# micro.net
KiCad netlist of a schematic drawn in Altium Designer
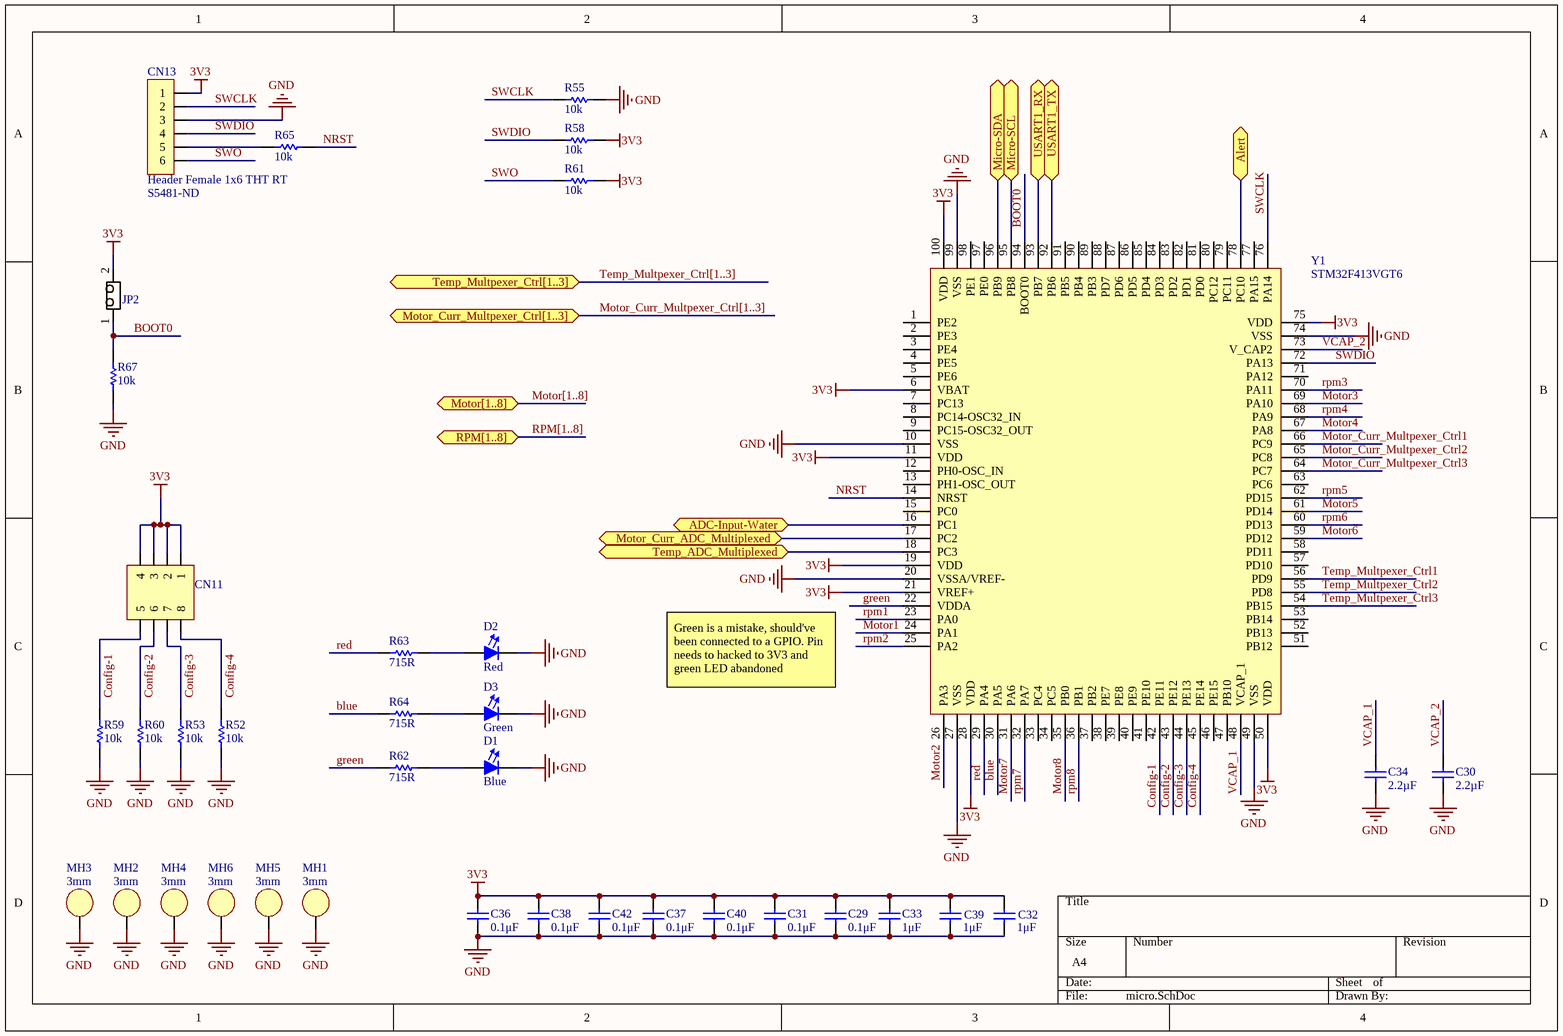
[diagram p0: micro.SchDoc]

(export (version "E")
  (design (tool "Eeschema 10.0.6"))
  (components
    (comp (ref "C29")
      (value "0.1μF")
      (footprint "CAPC1608N(0603\")")
      (description "Capacitor, Ceramic, 100V, +/- 10%, 0603 SMD, X7R")
      (fields
        (field (name "MFG") "TDK")
        (field (name "PUBLISHER") "AUVic")
        (field (name "CREATED BY") "Ashwin Sira")
      )
      (libsource (lib "AUVic_Integrated_Library_Capacitors") (part "0.1uF 100V 0603 SMD, Ceramic"))
    )
    (comp (ref "C30")
      (value "2.2µF")
      (footprint "CAPC1608N(0603\")")
      (description "Capacitor, Ceramic, 50V, 10%, 0603 SMD, X5R")
      (fields (field (name "MADE BY") "*") (field (name "PUBLISHER") "AUVic"))
      (libsource (lib "AUVic_Integrated_Library_Capacitors") (part "2.2uF, 50V, 0603 SMD, X5R, Ceramic"))
    )
    (comp (ref "C31")
      (value "0.1μF")
      (footprint "CAPC1608N(0603\")")
      (description "Capacitor, Ceramic, 100V, +/- 10%, 0603 SMD, X7R")
      (fields
        (field (name "MFG") "TDK")
        (field (name "PUBLISHER") "AUVic")
        (field (name "CREATED BY") "Ashwin Sira")
      )
      (libsource (lib "AUVic_Integrated_Library_Capacitors") (part "0.1uF 100V 0603 SMD, Ceramic"))
    )
    (comp (ref "C32")
      (value "1μF")
      (footprint "CAPC1608N(0603\")")
      (description "Capacitor, Ceramic, 25V, +/- 10%, 0603 SMD, X5R")
      (fields
        (field (name "MFG") "Murata-Electronics-North-America")
        (field (name "PUBLISHER") "AUVic")
        (field (name "CREATED BY") "Andy Bates")
      )
      (libsource (lib "AUVic_Integrated_Library_Capacitors") (part "1uF 25V 0603 SMD, Ceramic"))
    )
    (comp (ref "C33")
      (value "1μF")
      (footprint "CAPC1608N(0603\")")
      (description "Capacitor, Ceramic, 25V, +/- 10%, 0603 SMD, X5R")
      (fields
        (field (name "MFG") "Murata-Electronics-North-America")
        (field (name "PUBLISHER") "AUVic")
        (field (name "CREATED BY") "Andy Bates")
      )
      (libsource (lib "AUVic_Integrated_Library_Capacitors") (part "1uF 25V 0603 SMD, Ceramic"))
    )
    (comp (ref "C34")
      (value "2.2µF")
      (footprint "CAPC1608N(0603\")")
      (description "Capacitor, Ceramic, 50V, 10%, 0603 SMD, X5R")
      (fields (field (name "MADE BY") "*") (field (name "PUBLISHER") "AUVic"))
      (libsource (lib "AUVic_Integrated_Library_Capacitors") (part "2.2uF, 50V, 0603 SMD, X5R, Ceramic"))
    )
    (comp (ref "C36")
      (value "0.1μF")
      (footprint "CAPC1608N(0603\")")
      (description "Capacitor, Ceramic, 100V, +/- 10%, 0603 SMD, X7R")
      (fields
        (field (name "MFG") "TDK")
        (field (name "PUBLISHER") "AUVic")
        (field (name "CREATED BY") "Ashwin Sira")
      )
      (libsource (lib "AUVic_Integrated_Library_Capacitors") (part "0.1uF 100V 0603 SMD, Ceramic"))
    )
    (comp (ref "C37")
      (value "0.1μF")
      (footprint "CAPC1608N(0603\")")
      (description "Capacitor, Ceramic, 100V, +/- 10%, 0603 SMD, X7R")
      (fields
        (field (name "MFG") "TDK")
        (field (name "PUBLISHER") "AUVic")
        (field (name "CREATED BY") "Ashwin Sira")
      )
      (libsource (lib "AUVic_Integrated_Library_Capacitors") (part "0.1uF 100V 0603 SMD, Ceramic"))
    )
    (comp (ref "C38")
      (value "0.1μF")
      (footprint "CAPC1608N(0603\")")
      (description "Capacitor, Ceramic, 100V, +/- 10%, 0603 SMD, X7R")
      (fields
        (field (name "MFG") "TDK")
        (field (name "PUBLISHER") "AUVic")
        (field (name "CREATED BY") "Ashwin Sira")
      )
      (libsource (lib "AUVic_Integrated_Library_Capacitors") (part "0.1uF 100V 0603 SMD, Ceramic"))
    )
    (comp (ref "C39")
      (value "1μF")
      (footprint "CAPC1608N(0603\")")
      (description "Capacitor, Ceramic, 25V, +/- 10%, 0603 SMD, X5R")
      (fields
        (field (name "MFG") "Murata-Electronics-North-America")
        (field (name "PUBLISHER") "AUVic")
        (field (name "CREATED BY") "Andy Bates")
      )
      (libsource (lib "AUVic_Integrated_Library_Capacitors") (part "1uF 25V 0603 SMD, Ceramic"))
    )
    (comp (ref "C40")
      (value "0.1μF")
      (footprint "CAPC1608N(0603\")")
      (description "Capacitor, Ceramic, 100V, +/- 10%, 0603 SMD, X7R")
      (fields
        (field (name "MFG") "TDK")
        (field (name "PUBLISHER") "AUVic")
        (field (name "CREATED BY") "Ashwin Sira")
      )
      (libsource (lib "AUVic_Integrated_Library_Capacitors") (part "0.1uF 100V 0603 SMD, Ceramic"))
    )
    (comp (ref "C42")
      (value "0.1μF")
      (footprint "CAPC1608N(0603\")")
      (description "Capacitor, Ceramic, 100V, +/- 10%, 0603 SMD, X7R")
      (fields
        (field (name "MFG") "TDK")
        (field (name "PUBLISHER") "AUVic")
        (field (name "CREATED BY") "Ashwin Sira")
      )
      (libsource (lib "AUVic_Integrated_Library_Capacitors") (part "0.1uF 100V 0603 SMD, Ceramic"))
    )
    (comp (ref "CN11")
      (value "Header, Male, 2x4, Pitch: 0.1\" (2.54mm), THT")
      (footprint "Header, Male, 2x4, Pitch: 0.1\" (2.54mm),THT")
      (fields
        (field (name "PUBLISHER") "AUVic")
        (field (name "REVIEWED BY") "*")
        (field (name "CREATED BY") "Andy Bates")
      )
      (libsource (lib "AUVic_Integrated_Library_Connectors") (part "Header, Male, 2x4, Pitch{colon} 0.1{dblquote} (2.54mm), THT"))
    )
    (comp (ref "CN13")
      (value "Header Female 1x6 THT RT")
      (footprint "Header, Female, RT Ang, 0.1\", 1X6")
      (description "1x4, Pads Pitch: 0.1\" (2.54mm), RT Ang, Through hole")
      (fields (field (name "SUPPLIER PART NUMBER 1") "S5481-ND"))
      (libsource (lib "AUVic_Integrated_Library_Connectors") (part "Header, Female, 1x6,THT"))
    )
    (comp (ref "D1")
      (value "Blue")
      (footprint "LED0805")
      (description "LED, 0805 (2012), Blue, Clear")
      (fields (field (name "CREATED BY") "Ashwin Sira"))
      (libsource (lib "AUVic_Integrated_Library_Diodes") (part "LED, 0805 (2012), Blue, Clear"))
    )
    (comp (ref "D2")
      (value "Red")
      (footprint "LED0805")
      (description "LED, 0805 (2012), Red, Clear")
      (fields (field (name "CREATED BY") "Ashwin Sira"))
      (libsource (lib "AUVic_Schematic_Library_Diodes") (part "LED, 0805 (2012), Red, Clear"))
    )
    (comp (ref "D3")
      (value "Green")
      (footprint "LED0805")
      (description "LED, 0805 (2012), Green, Clear")
      (fields (field (name "CREATED BY") "Andy Bates"))
      (libsource (lib "AUVic_Integrated_Library_Diodes") (part "LED, 0805 (2012), Green, Clear"))
    )
    (comp (ref "JP2")
      (value "1X2 Pin Head")
      (footprint "2X1 Males Header")
      (fields (field (name "MADE BY") "Andy Bates"))
      (libsource (lib "AUVic_Schematic_Library_Connectors") (part "1x2 Male Header"))
    )
    (comp (ref "MH1")
      (value "3mm")
      (footprint "Mount-Hole_3mm")
      (libsource (lib "AUVic_Integrated_Library_Connectors") (part "Mount_Hole_3mm"))
    )
    (comp (ref "MH2")
      (value "3mm")
      (footprint "Mount-Hole_3mm")
      (libsource (lib "AUVic_Integrated_Library_Connectors") (part "Mount_Hole_3mm"))
    )
    (comp (ref "MH3")
      (value "3mm")
      (footprint "Mount-Hole_3mm")
      (libsource (lib "AUVic_Integrated_Library_Connectors") (part "Mount_Hole_3mm"))
    )
    (comp (ref "MH4")
      (value "3mm")
      (footprint "Mount-Hole_3mm")
      (libsource (lib "AUVic_Integrated_Library_Connectors") (part "Mount_Hole_3mm"))
    )
    (comp (ref "MH5")
      (value "3mm")
      (footprint "Mount-Hole_3mm")
      (libsource (lib "AUVic_Integrated_Library_Connectors") (part "Mount_Hole_3mm"))
    )
    (comp (ref "MH6")
      (value "3mm")
      (footprint "Mount-Hole_3mm")
      (libsource (lib "AUVic_Integrated_Library_Connectors") (part "Mount_Hole_3mm"))
    )
    (comp (ref "R52")
      (value "10k")
      (footprint "RESC1608N(0603\")")
      (description "10kR, 1%, 1/10W, 0603 SMD")
      (fields (field (name "MADE BY") "Ashwin Sira"))
      (libsource (lib "AUVic_Integrated_Library_Resistors") (part "10kR, 1%, 1/10W, 0603 SMD"))
    )
    (comp (ref "R53")
      (value "10k")
      (footprint "RESC1608N(0603\")")
      (description "10kR, 1%, 1/10W, 0603 SMD")
      (fields (field (name "MADE BY") "Ashwin Sira"))
      (libsource (lib "AUVic_Integrated_Library_Resistors") (part "10kR, 1%, 1/10W, 0603 SMD"))
    )
    (comp (ref "R55")
      (value "10k")
      (footprint "RESC1608N(0603\")")
      (description "10kR, 1%, 1/10W, 0603 SMD")
      (fields (field (name "MADE BY") "Ashwin Sira"))
      (libsource (lib "AUVic_Integrated_Library_Resistors") (part "10kR, 1%, 1/10W, 0603 SMD"))
    )
    (comp (ref "R58")
      (value "10k")
      (footprint "RESC1608N(0603\")")
      (description "10kR, 1%, 1/10W, 0603 SMD")
      (fields (field (name "MADE BY") "Ashwin Sira"))
      (libsource (lib "AUVic_Integrated_Library_Resistors") (part "10kR, 1%, 1/10W, 0603 SMD"))
    )
    (comp (ref "R59")
      (value "10k")
      (footprint "RESC1608N(0603\")")
      (description "10kR, 1%, 1/10W, 0603 SMD")
      (fields (field (name "MADE BY") "Ashwin Sira"))
      (libsource (lib "AUVic_Integrated_Library_Resistors") (part "10kR, 1%, 1/10W, 0603 SMD"))
    )
    (comp (ref "R60")
      (value "10k")
      (footprint "RESC1608N(0603\")")
      (description "10kR, 1%, 1/10W, 0603 SMD")
      (fields (field (name "MADE BY") "Ashwin Sira"))
      (libsource (lib "AUVic_Integrated_Library_Resistors") (part "10kR, 1%, 1/10W, 0603 SMD"))
    )
    (comp (ref "R61")
      (value "10k")
      (footprint "RESC1608N(0603\")")
      (description "10kR, 1%, 1/10W, 0603 SMD")
      (fields (field (name "MADE BY") "Ashwin Sira"))
      (libsource (lib "AUVic_Integrated_Library_Resistors") (part "10kR, 1%, 1/10W, 0603 SMD"))
    )
    (comp (ref "R62")
      (value "715R")
      (footprint "RESC1608N(0603\")")
      (description "715R, 1%, 1/10W, 0603, SMD")
      (fields (field (name "CREATED BY") "Ashwin Sira") (field (name "PUBLISHER") "AUVic"))
      (libsource (lib "AUVic_Integrated_Library_Resistors") (part "715R, 1%, 1/10W, 0603, SMD"))
    )
    (comp (ref "R63")
      (value "715R")
      (footprint "RESC1608N(0603\")")
      (description "715R, 1%, 1/10W, 0603, SMD")
      (fields (field (name "CREATED BY") "Ashwin Sira") (field (name "PUBLISHER") "AUVic"))
      (libsource (lib "AUVic_Integrated_Library_Resistors") (part "715R, 1%, 1/10W, 0603, SMD"))
    )
    (comp (ref "R64")
      (value "715R")
      (footprint "RESC1608N(0603\")")
      (description "715R, 1%, 1/10W, 0603, SMD")
      (fields (field (name "CREATED BY") "Ashwin Sira") (field (name "PUBLISHER") "AUVic"))
      (libsource (lib "AUVic_Integrated_Library_Resistors") (part "715R, 1%, 1/10W, 0603, SMD"))
    )
    (comp (ref "R65")
      (value "10k")
      (footprint "RESC1608N(0603\")")
      (description "10kR, 1%, 1/10W, 0603 SMD")
      (fields (field (name "MADE BY") "Ashwin Sira"))
      (libsource (lib "AUVic_Integrated_Library_Resistors") (part "10kR, 1%, 1/10W, 0603 SMD"))
    )
    (comp (ref "R67")
      (value "10k")
      (footprint "RESC1608N(0603\")")
      (description "10kR, 1%, 1/10W, 0603 SMD")
      (fields (field (name "MADE BY") "Ashwin Sira"))
      (libsource (lib "AUVic_Integrated_Library_Resistors") (part "10kR, 1%, 1/10W, 0603 SMD"))
    )
    (comp (ref "Y1")
      (value "STM32F413VGT6")
      (footprint "STM-LQFP100_M")
      (description "ARM Cortex-M4 32-bit MCU, 180 MHz, 320 KB Internal Rap, 81 I/O, 100-pin LQFP, -40 to 85 degC, Tray")
      (libsource (lib "AUVic_Integrated_Library_Microprocessors") (part "STM32F413VGT6"))
    )
  )
  (nets
    (net (code "9") (name "/ADC-Input-Water") (class "Default")
      (node (ref "Y1") (pin "16") (pinfunction "PC1_16") (pintype "passive"))
    )
    (net (code "10") (name "/Alert") (class "Default")
      (node (ref "Y1") (pin "78") (pinfunction "PC10_78") (pintype "passive"))
    )
    (net (code "11") (name "/BOOT0") (class "Default")
      (node (ref "JP2") (pin "1") (pinfunction "1_1") (pintype "passive"))
      (node (ref "R67") (pin "2") (pinfunction "2_2") (pintype "passive"))
      (node (ref "Y1") (pin "94") (pinfunction "BOOT0_94") (pintype "passive"))
    )
    (net (code "12") (name "/Config-1") (class "Default")
      (node (ref "CN11") (pin "5") (pinfunction "5_5") (pintype "passive"))
      (node (ref "R59") (pin "2") (pinfunction "2_2") (pintype "passive"))
      (node (ref "Y1") (pin "42") (pinfunction "PE11_42") (pintype "passive"))
    )
    (net (code "13") (name "/Config-2") (class "Default")
      (node (ref "CN11") (pin "6") (pinfunction "6_6") (pintype "passive"))
      (node (ref "R60") (pin "2") (pinfunction "2_2") (pintype "passive"))
      (node (ref "Y1") (pin "43") (pinfunction "PE12_43") (pintype "passive"))
    )
    (net (code "14") (name "/Config-3") (class "Default")
      (node (ref "CN11") (pin "7") (pinfunction "7_7") (pintype "passive"))
      (node (ref "R53") (pin "2") (pinfunction "2_2") (pintype "passive"))
      (node (ref "Y1") (pin "44") (pinfunction "PE13_44") (pintype "passive"))
    )
    (net (code "15") (name "/Config-4") (class "Default")
      (node (ref "CN11") (pin "8") (pinfunction "8_8") (pintype "passive"))
      (node (ref "R52") (pin "2") (pinfunction "2_2") (pintype "passive"))
      (node (ref "Y1") (pin "45") (pinfunction "PE14_45") (pintype "passive"))
    )
    (net (code "16") (name "/Micro-SCL") (class "Default")
      (node (ref "Y1") (pin "95") (pinfunction "PB8_95") (pintype "passive"))
    )
    (net (code "17") (name "/Micro-SDA") (class "Default")
      (node (ref "Y1") (pin "96") (pinfunction "PB9_96") (pintype "passive"))
    )
    (net (code "18") (name "/Motor1") (class "Default")
      (node (ref "Y1") (pin "24") (pinfunction "PA1_24") (pintype "passive"))
    )
    (net (code "19") (name "/Motor2") (class "Default")
      (node (ref "Y1") (pin "26") (pinfunction "PA3_26") (pintype "passive"))
    )
    (net (code "20") (name "/Motor3") (class "Default")
      (node (ref "Y1") (pin "69") (pinfunction "PA10_69") (pintype "passive"))
    )
    (net (code "21") (name "/Motor4") (class "Default")
      (node (ref "Y1") (pin "67") (pinfunction "PA8_67") (pintype "passive"))
    )
    (net (code "22") (name "/Motor5") (class "Default")
      (node (ref "Y1") (pin "61") (pinfunction "PD14_61") (pintype "passive"))
    )
    (net (code "23") (name "/Motor6") (class "Default")
      (node (ref "Y1") (pin "59") (pinfunction "PD12_59") (pintype "passive"))
    )
    (net (code "24") (name "/Motor7") (class "Default")
      (node (ref "Y1") (pin "31") (pinfunction "PA6_31") (pintype "passive"))
    )
    (net (code "25") (name "/Motor8") (class "Default")
      (node (ref "Y1") (pin "35") (pinfunction "PB0_35") (pintype "passive"))
    )
    (net (code "27") (name "/Motor_Curr_ADC_Multiplexed") (class "Default")
      (node (ref "Y1") (pin "17") (pinfunction "PC2_17") (pintype "passive"))
    )
    (net (code "28") (name "/Motor_Curr_Multpexer_Ctrl1") (class "Default")
      (node (ref "Y1") (pin "66") (pinfunction "PC9_66") (pintype "passive"))
    )
    (net (code "29") (name "/Motor_Curr_Multpexer_Ctrl2") (class "Default")
      (node (ref "Y1") (pin "65") (pinfunction "PC8_65") (pintype "passive"))
    )
    (net (code "30") (name "/Motor_Curr_Multpexer_Ctrl3") (class "Default")
      (node (ref "Y1") (pin "64") (pinfunction "PC7_64") (pintype "passive"))
    )
    (net (code "32") (name "/NRST") (class "Default")
      (node (ref "R65") (pin "2") (pinfunction "2_2") (pintype "passive"))
      (node (ref "Y1") (pin "14") (pinfunction "NRST_14") (pintype "passive"))
    )
    (net (code "34") (name "/SWCLK") (class "Default")
      (node (ref "CN13") (pin "2") (pinfunction "2_2") (pintype "passive"))
      (node (ref "R55") (pin "2") (pinfunction "2_2") (pintype "passive"))
      (node (ref "Y1") (pin "76") (pinfunction "PA14_76") (pintype "passive"))
    )
    (net (code "35") (name "/SWDIO") (class "Default")
      (node (ref "CN13") (pin "4") (pinfunction "4_4") (pintype "passive"))
      (node (ref "R58") (pin "1") (pinfunction "1_1") (pintype "passive"))
      (node (ref "Y1") (pin "72") (pinfunction "PA13_72") (pintype "passive"))
    )
    (net (code "36") (name "/SWO") (class "Default")
      (node (ref "CN13") (pin "6") (pinfunction "6_6") (pintype "passive"))
      (node (ref "R61") (pin "1") (pinfunction "1_1") (pintype "passive"))
    )
    (net (code "37") (name "/Temp_ADC_Multiplexed") (class "Default")
      (node (ref "Y1") (pin "18") (pinfunction "PC3_18") (pintype "passive"))
    )
    (net (code "38") (name "/Temp_Multpexer_Ctrl1") (class "Default")
      (node (ref "Y1") (pin "56") (pinfunction "PD9_56") (pintype "passive"))
    )
    (net (code "39") (name "/Temp_Multpexer_Ctrl2") (class "Default")
      (node (ref "Y1") (pin "55") (pinfunction "PD8_55") (pintype "passive"))
    )
    (net (code "40") (name "/Temp_Multpexer_Ctrl3") (class "Default")
      (node (ref "Y1") (pin "54") (pinfunction "PB15_54") (pintype "passive"))
    )
    (net (code "42") (name "/USART1_RX") (class "Default")
      (node (ref "Y1") (pin "93") (pinfunction "PB7_93") (pintype "passive"))
    )
    (net (code "43") (name "/USART1_TX") (class "Default")
      (node (ref "Y1") (pin "92") (pinfunction "PB6_92") (pintype "passive"))
    )
    (net (code "44") (name "/VCAP_1") (class "Default")
      (node (ref "C34") (pin "2") (pinfunction "Cathode_2") (pintype "passive"))
      (node (ref "Y1") (pin "48") (pinfunction "VCAP_1_48") (pintype "passive"))
    )
    (net (code "45") (name "/VCAP_2") (class "Default")
      (node (ref "C30") (pin "2") (pinfunction "Cathode_2") (pintype "passive"))
      (node (ref "Y1") (pin "73") (pinfunction "V_CAP2_73") (pintype "passive"))
    )
    (net (code "46") (name "/blue") (class "Default")
      (node (ref "R64") (pin "2") (pinfunction "2_2") (pintype "passive"))
      (node (ref "Y1") (pin "30") (pinfunction "PA5_30") (pintype "passive"))
    )
    (net (code "47") (name "/green") (class "Default")
      (node (ref "R62") (pin "2") (pinfunction "2_2") (pintype "passive"))
      (node (ref "Y1") (pin "22") (pinfunction "VDDA_22") (pintype "passive"))
    )
    (net (code "48") (name "/red") (class "Default")
      (node (ref "R63") (pin "2") (pinfunction "2_2") (pintype "passive"))
      (node (ref "Y1") (pin "29") (pinfunction "PA4_29") (pintype "passive"))
    )
    (net (code "49") (name "/rpm1") (class "Default")
      (node (ref "Y1") (pin "23") (pinfunction "PA0_23") (pintype "passive"))
    )
    (net (code "50") (name "/rpm2") (class "Default")
      (node (ref "Y1") (pin "25") (pinfunction "PA2_25") (pintype "passive"))
    )
    (net (code "51") (name "/rpm3") (class "Default")
      (node (ref "Y1") (pin "70") (pinfunction "PA11_70") (pintype "passive"))
    )
    (net (code "52") (name "/rpm4") (class "Default")
      (node (ref "Y1") (pin "68") (pinfunction "PA9_68") (pintype "passive"))
    )
    (net (code "53") (name "/rpm5") (class "Default")
      (node (ref "Y1") (pin "62") (pinfunction "PD15_62") (pintype "passive"))
    )
    (net (code "54") (name "/rpm6") (class "Default")
      (node (ref "Y1") (pin "60") (pinfunction "PD13_60") (pintype "passive"))
    )
    (net (code "55") (name "/rpm7") (class "Default")
      (node (ref "Y1") (pin "32") (pinfunction "PA7_32") (pintype "passive"))
    )
    (net (code "56") (name "/rpm8") (class "Default")
      (node (ref "Y1") (pin "36") (pinfunction "PB1_36") (pintype "passive"))
    )
    (net (code "57") (name "3V3") (class "Default")
      (node (ref "C29") (pin "2") (pinfunction "Cathode_2") (pintype "passive"))
      (node (ref "C31") (pin "2") (pinfunction "Cathode_2") (pintype "passive"))
      (node (ref "C32") (pin "2") (pinfunction "Cathode_2") (pintype "passive"))
      (node (ref "C33") (pin "2") (pinfunction "Cathode_2") (pintype "passive"))
      (node (ref "C36") (pin "2") (pinfunction "Cathode_2") (pintype "passive"))
      (node (ref "C37") (pin "2") (pinfunction "Cathode_2") (pintype "passive"))
      (node (ref "C38") (pin "2") (pinfunction "Cathode_2") (pintype "passive"))
      (node (ref "C39") (pin "2") (pinfunction "Cathode_2") (pintype "passive"))
      (node (ref "C40") (pin "2") (pinfunction "Cathode_2") (pintype "passive"))
      (node (ref "C42") (pin "2") (pinfunction "Cathode_2") (pintype "passive"))
      (node (ref "CN11") (pin "1") (pinfunction "1_1") (pintype "passive"))
      (node (ref "CN11") (pin "2") (pinfunction "2_2") (pintype "passive"))
      (node (ref "CN11") (pin "3") (pinfunction "3_3") (pintype "passive"))
      (node (ref "CN11") (pin "4") (pinfunction "4_4") (pintype "passive"))
      (node (ref "CN13") (pin "1") (pinfunction "1_1") (pintype "passive"))
      (node (ref "JP2") (pin "2") (pinfunction "2_2") (pintype "passive"))
      (node (ref "R58") (pin "2") (pinfunction "2_2") (pintype "passive"))
      (node (ref "R61") (pin "2") (pinfunction "2_2") (pintype "passive"))
      (node (ref "Y1") (pin "100") (pinfunction "VDD_100") (pintype "passive"))
      (node (ref "Y1") (pin "11") (pinfunction "VDD_11") (pintype "passive"))
      (node (ref "Y1") (pin "19") (pinfunction "VDD_19") (pintype "passive"))
      (node (ref "Y1") (pin "21") (pinfunction "VREF+_21") (pintype "passive"))
      (node (ref "Y1") (pin "28") (pinfunction "VDD_28") (pintype "passive"))
      (node (ref "Y1") (pin "50") (pinfunction "VDD_50") (pintype "passive"))
      (node (ref "Y1") (pin "6") (pinfunction "VBAT_6") (pintype "passive"))
      (node (ref "Y1") (pin "75") (pinfunction "VDD_75") (pintype "passive"))
    )
    (net (code "58") (name "GND") (class "Default")
      (node (ref "C29") (pin "1") (pinfunction "Anode_1") (pintype "passive"))
      (node (ref "C30") (pin "1") (pinfunction "Anode_1") (pintype "passive"))
      (node (ref "C31") (pin "1") (pinfunction "Anode_1") (pintype "passive"))
      (node (ref "C32") (pin "1") (pinfunction "Anode_1") (pintype "passive"))
      (node (ref "C33") (pin "1") (pinfunction "Anode_1") (pintype "passive"))
      (node (ref "C34") (pin "1") (pinfunction "Anode_1") (pintype "passive"))
      (node (ref "C36") (pin "1") (pinfunction "Anode_1") (pintype "passive"))
      (node (ref "C37") (pin "1") (pinfunction "Anode_1") (pintype "passive"))
      (node (ref "C38") (pin "1") (pinfunction "Anode_1") (pintype "passive"))
      (node (ref "C39") (pin "1") (pinfunction "Anode_1") (pintype "passive"))
      (node (ref "C40") (pin "1") (pinfunction "Anode_1") (pintype "passive"))
      (node (ref "C42") (pin "1") (pinfunction "Anode_1") (pintype "passive"))
      (node (ref "CN13") (pin "3") (pinfunction "3_3") (pintype "passive"))
      (node (ref "D1") (pin "1") (pinfunction "Cathode_1") (pintype "passive"))
      (node (ref "D2") (pin "1") (pinfunction "Cathode_1") (pintype "passive"))
      (node (ref "D3") (pin "1") (pinfunction "Cathode_1") (pintype "passive"))
      (node (ref "MH1") (pin "1") (pinfunction "1_1") (pintype "passive"))
      (node (ref "MH2") (pin "1") (pinfunction "1_1") (pintype "passive"))
      (node (ref "MH3") (pin "1") (pinfunction "1_1") (pintype "passive"))
      (node (ref "MH4") (pin "1") (pinfunction "1_1") (pintype "passive"))
      (node (ref "MH5") (pin "1") (pinfunction "1_1") (pintype "passive"))
      (node (ref "MH6") (pin "1") (pinfunction "1_1") (pintype "passive"))
      (node (ref "R52") (pin "1") (pinfunction "1_1") (pintype "passive"))
      (node (ref "R53") (pin "1") (pinfunction "1_1") (pintype "passive"))
      (node (ref "R55") (pin "1") (pinfunction "1_1") (pintype "passive"))
      (node (ref "R59") (pin "1") (pinfunction "1_1") (pintype "passive"))
      (node (ref "R60") (pin "1") (pinfunction "1_1") (pintype "passive"))
      (node (ref "R67") (pin "1") (pinfunction "1_1") (pintype "passive"))
      (node (ref "Y1") (pin "10") (pinfunction "VSS_10") (pintype "passive"))
      (node (ref "Y1") (pin "20") (pinfunction "VSSA/VREF-_20") (pintype "passive"))
      (node (ref "Y1") (pin "27") (pinfunction "VSS_27") (pintype "passive"))
      (node (ref "Y1") (pin "49") (pinfunction "VSS_49") (pintype "passive"))
      (node (ref "Y1") (pin "74") (pinfunction "VSS_74") (pintype "passive"))
      (node (ref "Y1") (pin "99") (pinfunction "VSS_99") (pintype "passive"))
    )
    (net (code "59") (name "Net-(CN13-Pad5)") (class "Default")
      (node (ref "CN13") (pin "5") (pinfunction "5_5") (pintype "passive"))
      (node (ref "R65") (pin "1") (pinfunction "1_1") (pintype "passive"))
    )
    (net (code "60") (name "Net-(D1-Anode)") (class "Default")
      (node (ref "D1") (pin "2") (pinfunction "Anode_2") (pintype "passive"))
      (node (ref "R62") (pin "1") (pinfunction "1_1") (pintype "passive"))
    )
    (net (code "61") (name "Net-(D2-Anode)") (class "Default")
      (node (ref "D2") (pin "2") (pinfunction "Anode_2") (pintype "passive"))
      (node (ref "R63") (pin "1") (pinfunction "1_1") (pintype "passive"))
    )
    (net (code "62") (name "Net-(D3-Anode)") (class "Default")
      (node (ref "D3") (pin "2") (pinfunction "Anode_2") (pintype "passive"))
      (node (ref "R64") (pin "1") (pinfunction "1_1") (pintype "passive"))
    )
    (net (code "63") (name "unconnected-(Y1-PA12-Pad71)") (class "Default")
      (node (ref "Y1") (pin "71") (pinfunction "PA12_71") (pintype "passive"))
    )
    (net (code "64") (name "unconnected-(Y1-PA15-Pad77)") (class "Default")
      (node (ref "Y1") (pin "77") (pinfunction "PA15_77") (pintype "passive"))
    )
    (net (code "65") (name "unconnected-(Y1-PB2-Pad37)") (class "Default")
      (node (ref "Y1") (pin "37") (pinfunction "PB2_37") (pintype "passive"))
    )
    (net (code "66") (name "unconnected-(Y1-PB3-Pad89)") (class "Default")
      (node (ref "Y1") (pin "89") (pinfunction "PB3_89") (pintype "passive"))
    )
    (net (code "67") (name "unconnected-(Y1-PB4-Pad90)") (class "Default")
      (node (ref "Y1") (pin "90") (pinfunction "PB4_90") (pintype "passive"))
    )
    (net (code "68") (name "unconnected-(Y1-PB5-Pad91)") (class "Default")
      (node (ref "Y1") (pin "91") (pinfunction "PB5_91") (pintype "passive"))
    )
    (net (code "69") (name "unconnected-(Y1-PB10-Pad47)") (class "Default")
      (node (ref "Y1") (pin "47") (pinfunction "PB10_47") (pintype "passive"))
    )
    (net (code "70") (name "unconnected-(Y1-PB12-Pad51)") (class "Default")
      (node (ref "Y1") (pin "51") (pinfunction "PB12_51") (pintype "passive"))
    )
    (net (code "71") (name "unconnected-(Y1-PB13-Pad52)") (class "Default")
      (node (ref "Y1") (pin "52") (pinfunction "PB13_52") (pintype "passive"))
    )
    (net (code "72") (name "unconnected-(Y1-PB14-Pad53)") (class "Default")
      (node (ref "Y1") (pin "53") (pinfunction "PB14_53") (pintype "passive"))
    )
    (net (code "73") (name "unconnected-(Y1-PC0-Pad15)") (class "Default")
      (node (ref "Y1") (pin "15") (pinfunction "PC0_15") (pintype "passive"))
    )
    (net (code "74") (name "unconnected-(Y1-PC4-Pad33)") (class "Default")
      (node (ref "Y1") (pin "33") (pinfunction "PC4_33") (pintype "passive"))
    )
    (net (code "75") (name "unconnected-(Y1-PC5-Pad34)") (class "Default")
      (node (ref "Y1") (pin "34") (pinfunction "PC5_34") (pintype "passive"))
    )
    (net (code "76") (name "unconnected-(Y1-PC6-Pad63)") (class "Default")
      (node (ref "Y1") (pin "63") (pinfunction "PC6_63") (pintype "passive"))
    )
    (net (code "77") (name "unconnected-(Y1-PC11-Pad79)") (class "Default")
      (node (ref "Y1") (pin "79") (pinfunction "PC11_79") (pintype "passive"))
    )
    (net (code "78") (name "unconnected-(Y1-PC12-Pad80)") (class "Default")
      (node (ref "Y1") (pin "80") (pinfunction "PC12_80") (pintype "passive"))
    )
    (net (code "79") (name "unconnected-(Y1-PC13-Pad7)") (class "Default")
      (node (ref "Y1") (pin "7") (pinfunction "PC13_7") (pintype "passive"))
    )
    (net (code "80") (name "unconnected-(Y1-PC14-OSC32_IN-Pad8)") (class "Default")
      (node (ref "Y1") (pin "8") (pinfunction "PC14-OSC32_IN_8") (pintype "passive"))
    )
    (net (code "81") (name "unconnected-(Y1-PC15-OSC32_OUT-Pad9)") (class "Default")
      (node (ref "Y1") (pin "9") (pinfunction "PC15-OSC32_OUT_9") (pintype "passive"))
    )
    (net (code "82") (name "unconnected-(Y1-PD0-Pad81)") (class "Default")
      (node (ref "Y1") (pin "81") (pinfunction "PD0_81") (pintype "passive"))
    )
    (net (code "83") (name "unconnected-(Y1-PD1-Pad82)") (class "Default")
      (node (ref "Y1") (pin "82") (pinfunction "PD1_82") (pintype "passive"))
    )
    (net (code "84") (name "unconnected-(Y1-PD2-Pad83)") (class "Default")
      (node (ref "Y1") (pin "83") (pinfunction "PD2_83") (pintype "passive"))
    )
    (net (code "85") (name "unconnected-(Y1-PD3-Pad84)") (class "Default")
      (node (ref "Y1") (pin "84") (pinfunction "PD3_84") (pintype "passive"))
    )
    (net (code "86") (name "unconnected-(Y1-PD4-Pad85)") (class "Default")
      (node (ref "Y1") (pin "85") (pinfunction "PD4_85") (pintype "passive"))
    )
    (net (code "87") (name "unconnected-(Y1-PD5-Pad86)") (class "Default")
      (node (ref "Y1") (pin "86") (pinfunction "PD5_86") (pintype "passive"))
    )
    (net (code "88") (name "unconnected-(Y1-PD6-Pad87)") (class "Default")
      (node (ref "Y1") (pin "87") (pinfunction "PD6_87") (pintype "passive"))
    )
    (net (code "89") (name "unconnected-(Y1-PD7-Pad88)") (class "Default")
      (node (ref "Y1") (pin "88") (pinfunction "PD7_88") (pintype "passive"))
    )
    (net (code "90") (name "unconnected-(Y1-PD10-Pad57)") (class "Default")
      (node (ref "Y1") (pin "57") (pinfunction "PD10_57") (pintype "passive"))
    )
    (net (code "91") (name "unconnected-(Y1-PD11-Pad58)") (class "Default")
      (node (ref "Y1") (pin "58") (pinfunction "PD11_58") (pintype "passive"))
    )
    (net (code "92") (name "unconnected-(Y1-PE0-Pad97)") (class "Default")
      (node (ref "Y1") (pin "97") (pinfunction "PE0_97") (pintype "passive"))
    )
    (net (code "93") (name "unconnected-(Y1-PE1-Pad98)") (class "Default")
      (node (ref "Y1") (pin "98") (pinfunction "PE1_98") (pintype "passive"))
    )
    (net (code "94") (name "unconnected-(Y1-PE2-Pad1)") (class "Default")
      (node (ref "Y1") (pin "1") (pinfunction "PE2_1") (pintype "passive"))
    )
    (net (code "95") (name "unconnected-(Y1-PE3-Pad2)") (class "Default")
      (node (ref "Y1") (pin "2") (pinfunction "PE3_2") (pintype "passive"))
    )
    (net (code "96") (name "unconnected-(Y1-PE4-Pad3)") (class "Default")
      (node (ref "Y1") (pin "3") (pinfunction "PE4_3") (pintype "passive"))
    )
    (net (code "97") (name "unconnected-(Y1-PE5-Pad4)") (class "Default")
      (node (ref "Y1") (pin "4") (pinfunction "PE5_4") (pintype "passive"))
    )
    (net (code "98") (name "unconnected-(Y1-PE6-Pad5)") (class "Default")
      (node (ref "Y1") (pin "5") (pinfunction "PE6_5") (pintype "passive"))
    )
    (net (code "99") (name "unconnected-(Y1-PE7-Pad38)") (class "Default")
      (node (ref "Y1") (pin "38") (pinfunction "PE7_38") (pintype "passive"))
    )
    (net (code "100") (name "unconnected-(Y1-PE8-Pad39)") (class "Default")
      (node (ref "Y1") (pin "39") (pinfunction "PE8_39") (pintype "passive"))
    )
    (net (code "101") (name "unconnected-(Y1-PE9-Pad40)") (class "Default")
      (node (ref "Y1") (pin "40") (pinfunction "PE9_40") (pintype "passive"))
    )
    (net (code "102") (name "unconnected-(Y1-PE10-Pad41)") (class "Default")
      (node (ref "Y1") (pin "41") (pinfunction "PE10_41") (pintype "passive"))
    )
    (net (code "103") (name "unconnected-(Y1-PE15-Pad46)") (class "Default")
      (node (ref "Y1") (pin "46") (pinfunction "PE15_46") (pintype "passive"))
    )
    (net (code "104") (name "unconnected-(Y1-PH0-OSC_IN-Pad12)") (class "Default")
      (node (ref "Y1") (pin "12") (pinfunction "PH0-OSC_IN_12") (pintype "passive"))
    )
    (net (code "105") (name "unconnected-(Y1-PH1-OSC_OUT-Pad13)") (class "Default")
      (node (ref "Y1") (pin "13") (pinfunction "PH1-OSC_OUT_13") (pintype "passive"))
    )
  )
)
